# DDR4_SODIMM1.net
KiCad netlist of a schematic drawn in Altium Designer
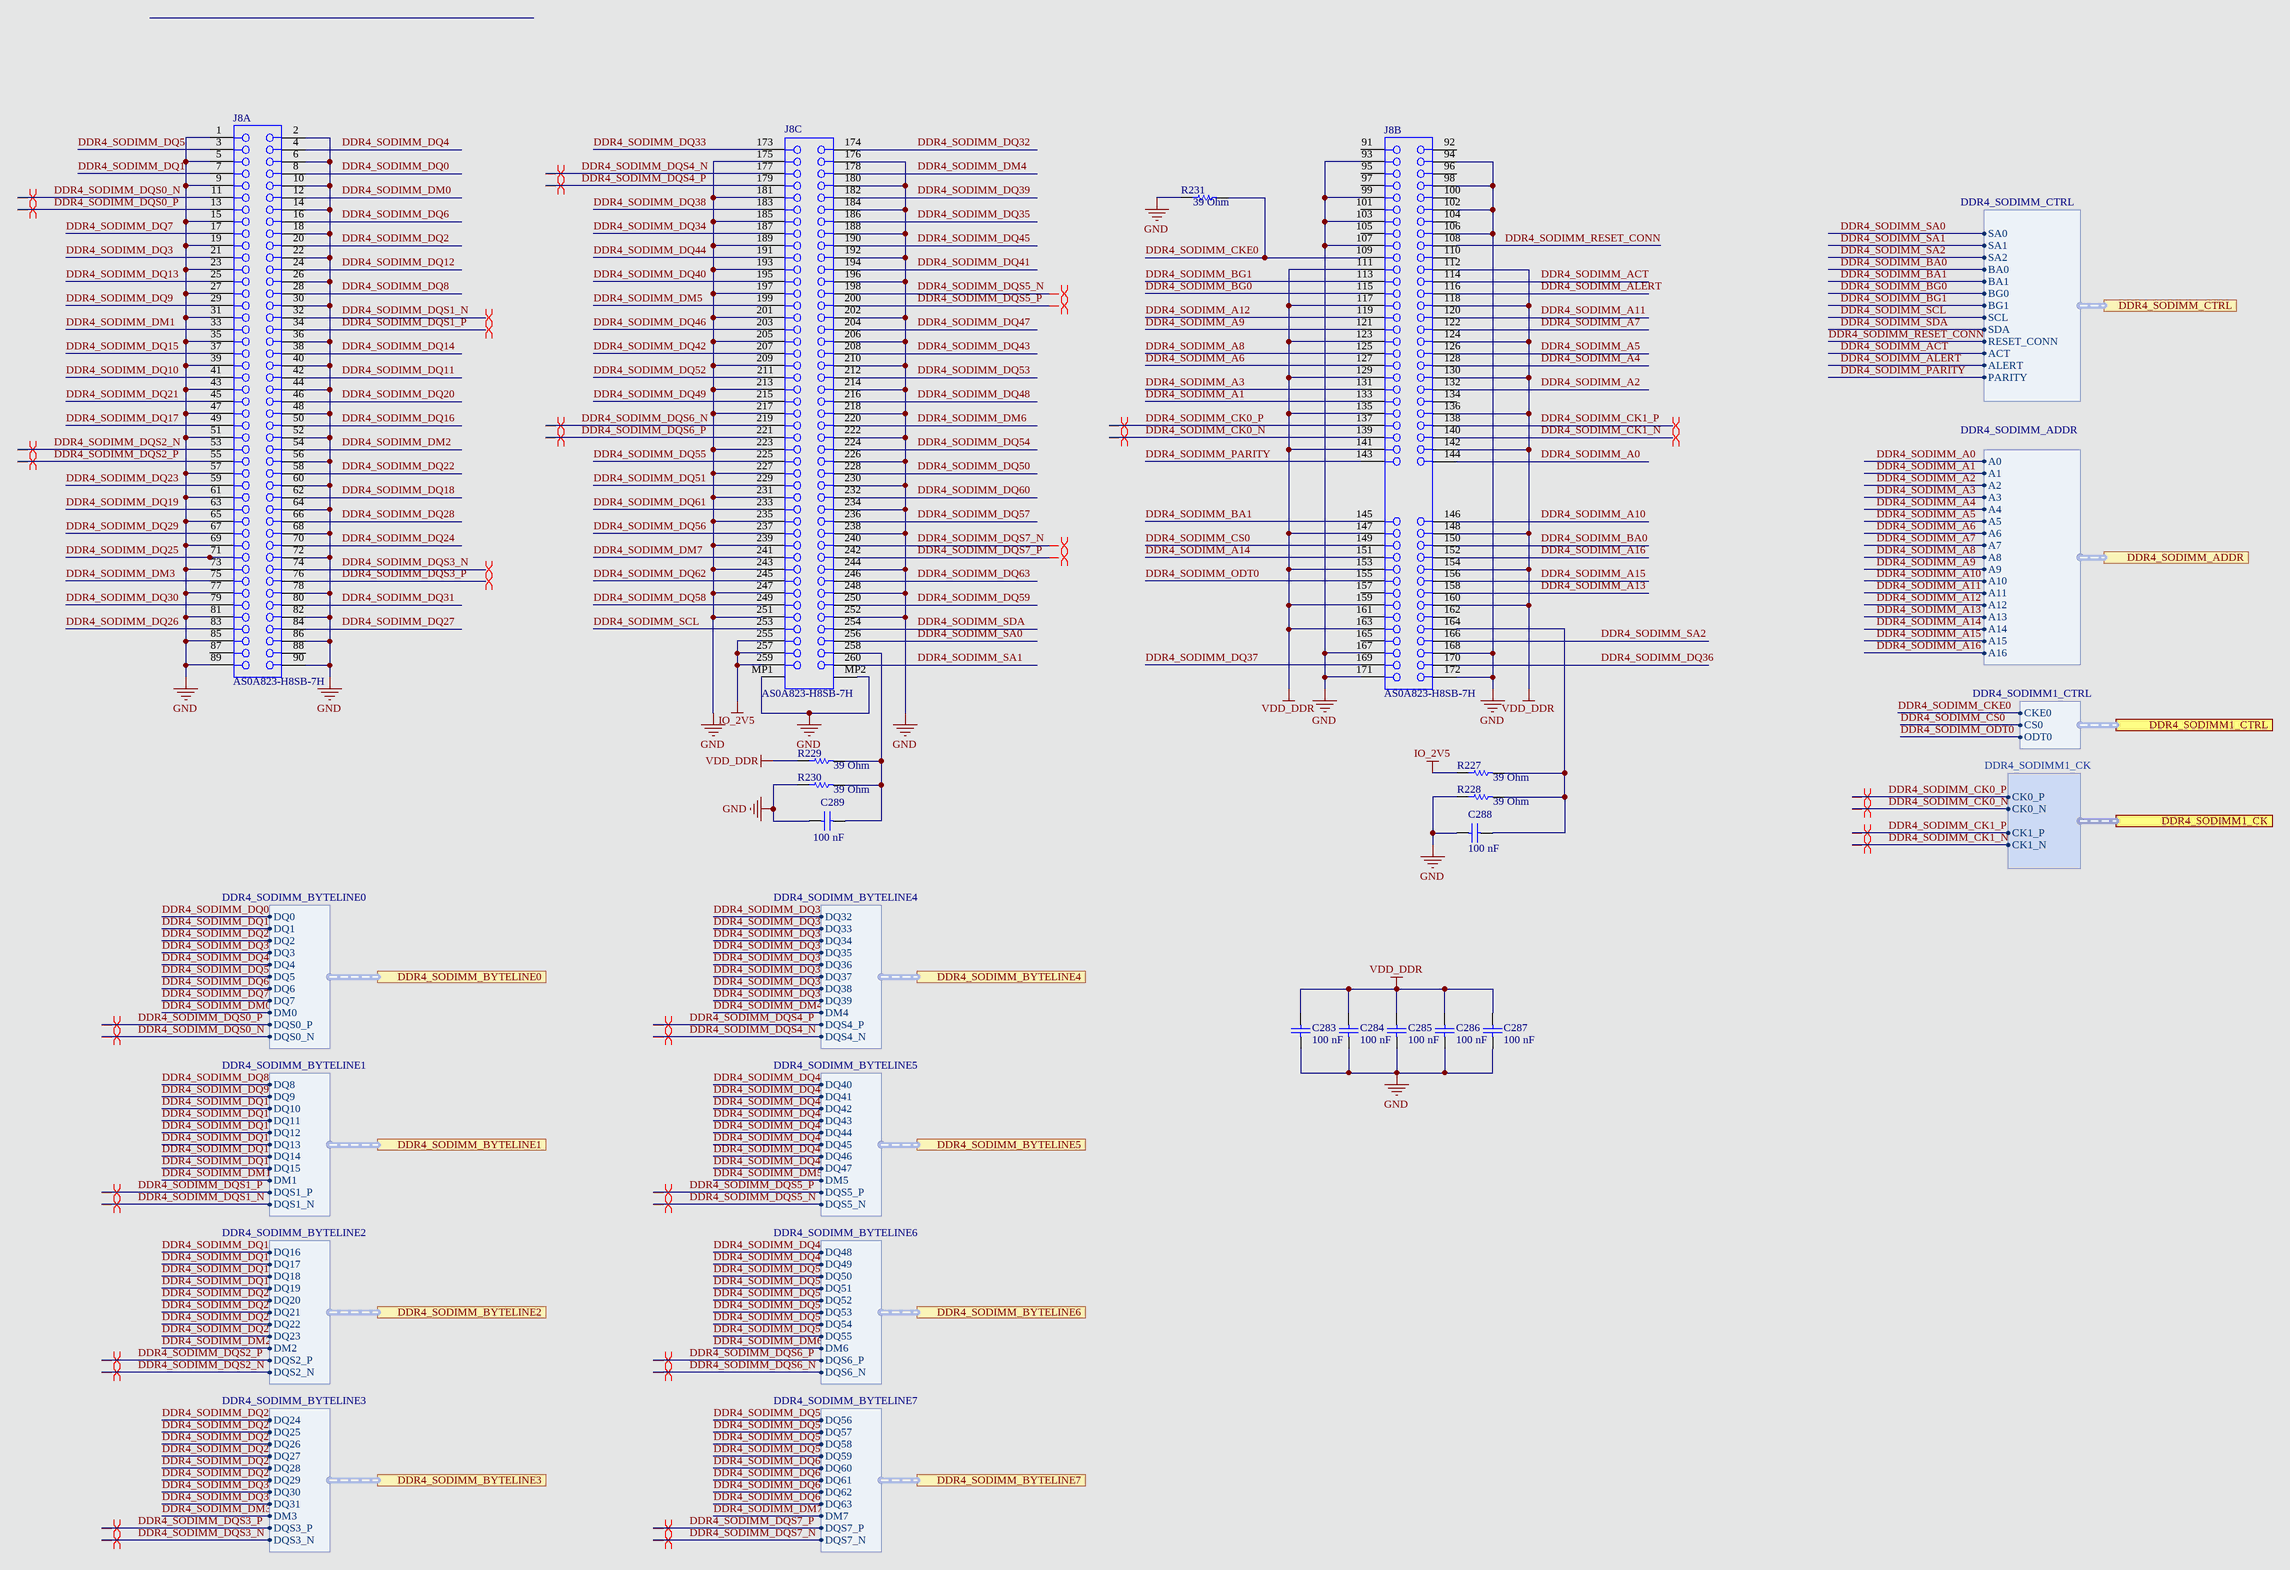
[diagram p0: DDR4_SODIMM1.SchDoc]

(export (version "E")
  (design (tool "Eeschema 10.0.6"))
  (components
    (comp (ref "C283")
      (value "C1005X7R1E104M")
      (footprint "CAPC1005X55X10LL05")
      (description "Chip Capacitor, 0.1 uF, +/- 20%, 25 V, -55 to 125 degC, 0402 (1005 Metric), RoHS, Tape and Reel")
      (fields (field (name "TOLERANCE") "20%") (field (name "CAPACITANCE") "100 nF"))
      (libsource (lib "Altium Content Vault") (part "CAP-NP-2"))
    )
    (comp (ref "C284")
      (value "C1005X7R1E104M")
      (footprint "CAPC1005X55X10LL05")
      (description "Chip Capacitor, 0.1 uF, +/- 20%, 25 V, -55 to 125 degC, 0402 (1005 Metric), RoHS, Tape and Reel")
      (fields (field (name "TOLERANCE") "20%") (field (name "CAPACITANCE") "100 nF"))
      (libsource (lib "Altium Content Vault") (part "CAP-NP-2"))
    )
    (comp (ref "C285")
      (value "C1005X7R1E104M")
      (footprint "CAPC1005X55X10LL05")
      (description "Chip Capacitor, 0.1 uF, +/- 20%, 25 V, -55 to 125 degC, 0402 (1005 Metric), RoHS, Tape and Reel")
      (fields (field (name "TOLERANCE") "20%") (field (name "CAPACITANCE") "100 nF"))
      (libsource (lib "Altium Content Vault") (part "CAP-NP-2"))
    )
    (comp (ref "C286")
      (value "C1005X7R1E104M")
      (footprint "CAPC1005X55X10LL05")
      (description "Chip Capacitor, 0.1 uF, +/- 20%, 25 V, -55 to 125 degC, 0402 (1005 Metric), RoHS, Tape and Reel")
      (fields (field (name "TOLERANCE") "20%") (field (name "CAPACITANCE") "100 nF"))
      (libsource (lib "Altium Content Vault") (part "CAP-NP-2"))
    )
    (comp (ref "C287")
      (value "C1005X7R1E104M")
      (footprint "CAPC1005X55X10LL05")
      (description "Chip Capacitor, 0.1 uF, +/- 20%, 25 V, -55 to 125 degC, 0402 (1005 Metric), RoHS, Tape and Reel")
      (fields (field (name "TOLERANCE") "20%") (field (name "CAPACITANCE") "100 nF"))
      (libsource (lib "Altium Content Vault") (part "CAP-NP-2"))
    )
    (comp (ref "C288")
      (value "C1005X7R1E104M")
      (footprint "CAPC1005X55X10LL05")
      (description "Chip Capacitor, 0.1 uF, +/- 20%, 25 V, -55 to 125 degC, 0402 (1005 Metric), RoHS, Tape and Reel")
      (fields (field (name "TOLERANCE") "20%") (field (name "CAPACITANCE") "100 nF"))
      (libsource (lib "Altium Content Vault") (part "CAP-NP-2"))
    )
    (comp (ref "C289")
      (value "C1005X7R1E104M")
      (footprint "CAPC1005X55X10LL05")
      (description "Chip Capacitor, 0.1 uF, +/- 20%, 25 V, -55 to 125 degC, 0402 (1005 Metric), RoHS, Tape and Reel")
      (fields (field (name "TOLERANCE") "20%") (field (name "CAPACITANCE") "100 nF"))
      (libsource (lib "Altium Content Vault") (part "CAP-NP-2"))
    )
    (comp (ref "J8")
      (value "AS0A823-H8SB-7H")
      (footprint "FOXC-AS0A823-H8SB-7H_V")
      (libsource (lib "") (part "CN-2S-2F-R260_1"))
    )
    (comp (ref "R227")
      (value "RC0402JR-0739RL")
      (footprint "RESC1005X40X25NL5T10")
      (description "Chip Resistor, 39 Ohm, +/- 5%, 0.063 W, -55 to 155 degC, 0402 (1005 Metric), RoHS, Tape and Reel")
      (fields (field (name "TOLERANCE") "5%") (field (name "RESISTANCE") "39 Ohm"))
      (libsource (lib "Altium Content Vault") (part "CMP-2002-07994-2"))
    )
    (comp (ref "R228")
      (value "RC0402JR-0739RL")
      (footprint "RESC1005X40X25NL5T10")
      (description "Chip Resistor, 39 Ohm, +/- 5%, 0.063 W, -55 to 155 degC, 0402 (1005 Metric), RoHS, Tape and Reel")
      (fields (field (name "TOLERANCE") "5%") (field (name "RESISTANCE") "39 Ohm"))
      (libsource (lib "Altium Content Vault") (part "CMP-2002-07994-2"))
    )
    (comp (ref "R229")
      (value "RC0402JR-0739RL")
      (footprint "RESC1005X40X25NL5T10")
      (description "Chip Resistor, 39 Ohm, +/- 5%, 0.063 W, -55 to 155 degC, 0402 (1005 Metric), RoHS, Tape and Reel")
      (fields (field (name "TOLERANCE") "5%") (field (name "RESISTANCE") "39 Ohm"))
      (libsource (lib "Altium Content Vault") (part "CMP-2002-07994-2"))
    )
    (comp (ref "R230")
      (value "RC0402JR-0739RL")
      (footprint "RESC1005X40X25NL5T10")
      (description "Chip Resistor, 39 Ohm, +/- 5%, 0.063 W, -55 to 155 degC, 0402 (1005 Metric), RoHS, Tape and Reel")
      (fields (field (name "TOLERANCE") "5%") (field (name "RESISTANCE") "39 Ohm"))
      (libsource (lib "Altium Content Vault") (part "CMP-2002-07994-2"))
    )
    (comp (ref "R231")
      (value "RC0402JR-0739RL")
      (footprint "RESC1005X40X25NL5T10")
      (description "Chip Resistor, 39 Ohm, +/- 5%, 0.063 W, -55 to 155 degC, 0402 (1005 Metric), RoHS, Tape and Reel")
      (fields (field (name "TOLERANCE") "5%") (field (name "RESISTANCE") "39 Ohm"))
      (libsource (lib "Altium Content Vault") (part "CMP-2002-07994-2"))
    )
  )
  (nets
    (net (code "13") (name "/DDR4_SODIMM_A0") (class "Default")
      (node (ref "J8") (pin "144") (pinfunction "144_144") (pintype "passive"))
    )
    (net (code "14") (name "/DDR4_SODIMM_A1") (class "Default")
      (node (ref "J8") (pin "133") (pinfunction "133_133") (pintype "passive"))
    )
    (net (code "15") (name "/DDR4_SODIMM_A2") (class "Default")
      (node (ref "J8") (pin "132") (pinfunction "132_132") (pintype "passive"))
    )
    (net (code "16") (name "/DDR4_SODIMM_A3") (class "Default")
      (node (ref "J8") (pin "131") (pinfunction "131_131") (pintype "passive"))
    )
    (net (code "17") (name "/DDR4_SODIMM_A4") (class "Default")
      (node (ref "J8") (pin "128") (pinfunction "128_128") (pintype "passive"))
    )
    (net (code "18") (name "/DDR4_SODIMM_A5") (class "Default")
      (node (ref "J8") (pin "126") (pinfunction "126_126") (pintype "passive"))
    )
    (net (code "19") (name "/DDR4_SODIMM_A6") (class "Default")
      (node (ref "J8") (pin "127") (pinfunction "127_127") (pintype "passive"))
    )
    (net (code "20") (name "/DDR4_SODIMM_A7") (class "Default")
      (node (ref "J8") (pin "122") (pinfunction "122_122") (pintype "passive"))
    )
    (net (code "21") (name "/DDR4_SODIMM_A8") (class "Default")
      (node (ref "J8") (pin "125") (pinfunction "125_125") (pintype "passive"))
    )
    (net (code "22") (name "/DDR4_SODIMM_A9") (class "Default")
      (node (ref "J8") (pin "121") (pinfunction "121_121") (pintype "passive"))
    )
    (net (code "23") (name "/DDR4_SODIMM_A10") (class "Default")
      (node (ref "J8") (pin "146") (pinfunction "146_146") (pintype "passive"))
    )
    (net (code "24") (name "/DDR4_SODIMM_A11") (class "Default")
      (node (ref "J8") (pin "120") (pinfunction "120_120") (pintype "passive"))
    )
    (net (code "25") (name "/DDR4_SODIMM_A12") (class "Default")
      (node (ref "J8") (pin "119") (pinfunction "119_119") (pintype "passive"))
    )
    (net (code "26") (name "/DDR4_SODIMM_A13") (class "Default")
      (node (ref "J8") (pin "158") (pinfunction "158_158") (pintype "passive"))
    )
    (net (code "27") (name "/DDR4_SODIMM_A14") (class "Default")
      (node (ref "J8") (pin "151") (pinfunction "151_151") (pintype "passive"))
    )
    (net (code "28") (name "/DDR4_SODIMM_A15") (class "Default")
      (node (ref "J8") (pin "156") (pinfunction "156_156") (pintype "passive"))
    )
    (net (code "29") (name "/DDR4_SODIMM_A16") (class "Default")
      (node (ref "J8") (pin "152") (pinfunction "152_152") (pintype "passive"))
    )
    (net (code "30") (name "/DDR4_SODIMM_ACT") (class "Default")
      (node (ref "J8") (pin "114") (pinfunction "114_114") (pintype "passive"))
    )
    (net (code "31") (name "/DDR4_SODIMM_ALERT") (class "Default")
      (node (ref "J8") (pin "116") (pinfunction "116_116") (pintype "passive"))
    )
    (net (code "32") (name "/DDR4_SODIMM_BA0") (class "Default")
      (node (ref "J8") (pin "150") (pinfunction "150_150") (pintype "passive"))
    )
    (net (code "33") (name "/DDR4_SODIMM_BA1") (class "Default")
      (node (ref "J8") (pin "145") (pinfunction "145_145") (pintype "passive"))
    )
    (net (code "34") (name "/DDR4_SODIMM_BG0") (class "Default")
      (node (ref "J8") (pin "115") (pinfunction "115_115") (pintype "passive"))
    )
    (net (code "35") (name "/DDR4_SODIMM_BG1") (class "Default")
      (node (ref "J8") (pin "113") (pinfunction "113_113") (pintype "passive"))
    )
    (net (code "36") (name "/DDR4_SODIMM_CK0_N") (class "Default")
      (node (ref "J8") (pin "139") (pinfunction "139_139") (pintype "passive"))
    )
    (net (code "37") (name "/DDR4_SODIMM_CK0_P") (class "Default")
      (node (ref "J8") (pin "137") (pinfunction "137_137") (pintype "passive"))
    )
    (net (code "38") (name "/DDR4_SODIMM_CK1_N") (class "Default")
      (node (ref "J8") (pin "140") (pinfunction "140_140") (pintype "passive"))
    )
    (net (code "39") (name "/DDR4_SODIMM_CK1_P") (class "Default")
      (node (ref "J8") (pin "138") (pinfunction "138_138") (pintype "passive"))
    )
    (net (code "40") (name "/DDR4_SODIMM_CKE0") (class "Default")
      (node (ref "J8") (pin "109") (pinfunction "109_109") (pintype "passive"))
      (node (ref "R231") (pin "2") (pinfunction "2_2") (pintype "passive"))
    )
    (net (code "41") (name "/DDR4_SODIMM_CS0") (class "Default")
      (node (ref "J8") (pin "149") (pinfunction "149_149") (pintype "passive"))
    )
    (net (code "42") (name "/DDR4_SODIMM_DM0") (class "Default")
      (node (ref "J8") (pin "12") (pinfunction "12_12") (pintype "passive"))
    )
    (net (code "43") (name "/DDR4_SODIMM_DM1") (class "Default")
      (node (ref "J8") (pin "33") (pinfunction "33_33") (pintype "passive"))
    )
    (net (code "44") (name "/DDR4_SODIMM_DM2") (class "Default")
      (node (ref "J8") (pin "54") (pinfunction "54_54") (pintype "passive"))
    )
    (net (code "45") (name "/DDR4_SODIMM_DM3") (class "Default")
      (node (ref "J8") (pin "75") (pinfunction "75_75") (pintype "passive"))
    )
    (net (code "46") (name "/DDR4_SODIMM_DM4") (class "Default")
      (node (ref "J8") (pin "178") (pinfunction "178_178") (pintype "passive"))
    )
    (net (code "47") (name "/DDR4_SODIMM_DM5") (class "Default")
      (node (ref "J8") (pin "199") (pinfunction "199_199") (pintype "passive"))
    )
    (net (code "48") (name "/DDR4_SODIMM_DM6") (class "Default")
      (node (ref "J8") (pin "220") (pinfunction "220_220") (pintype "passive"))
    )
    (net (code "49") (name "/DDR4_SODIMM_DM7") (class "Default")
      (node (ref "J8") (pin "241") (pinfunction "241_241") (pintype "passive"))
    )
    (net (code "50") (name "/DDR4_SODIMM_DQ0") (class "Default")
      (node (ref "J8") (pin "8") (pinfunction "8_8") (pintype "passive"))
    )
    (net (code "51") (name "/DDR4_SODIMM_DQ1") (class "Default")
      (node (ref "J8") (pin "7") (pinfunction "7_7") (pintype "passive"))
    )
    (net (code "52") (name "/DDR4_SODIMM_DQ2") (class "Default")
      (node (ref "J8") (pin "20") (pinfunction "20_20") (pintype "passive"))
    )
    (net (code "53") (name "/DDR4_SODIMM_DQ3") (class "Default")
      (node (ref "J8") (pin "21") (pinfunction "21_21") (pintype "passive"))
    )
    (net (code "54") (name "/DDR4_SODIMM_DQ4") (class "Default")
      (node (ref "J8") (pin "4") (pinfunction "4_4") (pintype "passive"))
    )
    (net (code "55") (name "/DDR4_SODIMM_DQ5") (class "Default")
      (node (ref "J8") (pin "3") (pinfunction "3_3") (pintype "passive"))
    )
    (net (code "56") (name "/DDR4_SODIMM_DQ6") (class "Default")
      (node (ref "J8") (pin "16") (pinfunction "16_16") (pintype "passive"))
    )
    (net (code "57") (name "/DDR4_SODIMM_DQ7") (class "Default")
      (node (ref "J8") (pin "17") (pinfunction "17_17") (pintype "passive"))
    )
    (net (code "58") (name "/DDR4_SODIMM_DQ8") (class "Default")
      (node (ref "J8") (pin "28") (pinfunction "28_28") (pintype "passive"))
    )
    (net (code "59") (name "/DDR4_SODIMM_DQ9") (class "Default")
      (node (ref "J8") (pin "29") (pinfunction "29_29") (pintype "passive"))
    )
    (net (code "60") (name "/DDR4_SODIMM_DQ10") (class "Default")
      (node (ref "J8") (pin "41") (pinfunction "41_41") (pintype "passive"))
    )
    (net (code "61") (name "/DDR4_SODIMM_DQ11") (class "Default")
      (node (ref "J8") (pin "42") (pinfunction "42_42") (pintype "passive"))
    )
    (net (code "62") (name "/DDR4_SODIMM_DQ12") (class "Default")
      (node (ref "J8") (pin "24") (pinfunction "24_24") (pintype "passive"))
    )
    (net (code "63") (name "/DDR4_SODIMM_DQ13") (class "Default")
      (node (ref "J8") (pin "25") (pinfunction "25_25") (pintype "passive"))
    )
    (net (code "64") (name "/DDR4_SODIMM_DQ14") (class "Default")
      (node (ref "J8") (pin "38") (pinfunction "38_38") (pintype "passive"))
    )
    (net (code "65") (name "/DDR4_SODIMM_DQ15") (class "Default")
      (node (ref "J8") (pin "37") (pinfunction "37_37") (pintype "passive"))
    )
    (net (code "66") (name "/DDR4_SODIMM_DQ16") (class "Default")
      (node (ref "J8") (pin "50") (pinfunction "50_50") (pintype "passive"))
    )
    (net (code "67") (name "/DDR4_SODIMM_DQ17") (class "Default")
      (node (ref "J8") (pin "49") (pinfunction "49_49") (pintype "passive"))
    )
    (net (code "68") (name "/DDR4_SODIMM_DQ18") (class "Default")
      (node (ref "J8") (pin "62") (pinfunction "62_62") (pintype "passive"))
    )
    (net (code "69") (name "/DDR4_SODIMM_DQ19") (class "Default")
      (node (ref "J8") (pin "63") (pinfunction "63_63") (pintype "passive"))
    )
    (net (code "70") (name "/DDR4_SODIMM_DQ20") (class "Default")
      (node (ref "J8") (pin "46") (pinfunction "46_46") (pintype "passive"))
    )
    (net (code "71") (name "/DDR4_SODIMM_DQ21") (class "Default")
      (node (ref "J8") (pin "45") (pinfunction "45_45") (pintype "passive"))
    )
    (net (code "72") (name "/DDR4_SODIMM_DQ22") (class "Default")
      (node (ref "J8") (pin "58") (pinfunction "58_58") (pintype "passive"))
    )
    (net (code "73") (name "/DDR4_SODIMM_DQ23") (class "Default")
      (node (ref "J8") (pin "59") (pinfunction "59_59") (pintype "passive"))
    )
    (net (code "74") (name "/DDR4_SODIMM_DQ24") (class "Default")
      (node (ref "J8") (pin "70") (pinfunction "70_70") (pintype "passive"))
    )
    (net (code "75") (name "/DDR4_SODIMM_DQ25") (class "Default")
      (node (ref "J8") (pin "71") (pinfunction "71_71") (pintype "passive"))
    )
    (net (code "76") (name "/DDR4_SODIMM_DQ26") (class "Default")
      (node (ref "J8") (pin "83") (pinfunction "83_83") (pintype "passive"))
    )
    (net (code "77") (name "/DDR4_SODIMM_DQ27") (class "Default")
      (node (ref "J8") (pin "84") (pinfunction "84_84") (pintype "passive"))
    )
    (net (code "78") (name "/DDR4_SODIMM_DQ28") (class "Default")
      (node (ref "J8") (pin "66") (pinfunction "66_66") (pintype "passive"))
    )
    (net (code "79") (name "/DDR4_SODIMM_DQ29") (class "Default")
      (node (ref "J8") (pin "67") (pinfunction "67_67") (pintype "passive"))
    )
    (net (code "80") (name "/DDR4_SODIMM_DQ30") (class "Default")
      (node (ref "J8") (pin "79") (pinfunction "79_79") (pintype "passive"))
    )
    (net (code "81") (name "/DDR4_SODIMM_DQ31") (class "Default")
      (node (ref "J8") (pin "80") (pinfunction "80_80") (pintype "passive"))
    )
    (net (code "82") (name "/DDR4_SODIMM_DQ32") (class "Default")
      (node (ref "J8") (pin "174") (pinfunction "174_174") (pintype "passive"))
    )
    (net (code "83") (name "/DDR4_SODIMM_DQ33") (class "Default")
      (node (ref "J8") (pin "173") (pinfunction "173_173") (pintype "passive"))
    )
    (net (code "84") (name "/DDR4_SODIMM_DQ34") (class "Default")
      (node (ref "J8") (pin "187") (pinfunction "187_187") (pintype "passive"))
    )
    (net (code "85") (name "/DDR4_SODIMM_DQ35") (class "Default")
      (node (ref "J8") (pin "186") (pinfunction "186_186") (pintype "passive"))
    )
    (net (code "86") (name "/DDR4_SODIMM_DQ36") (class "Default")
      (node (ref "J8") (pin "170") (pinfunction "170_170") (pintype "passive"))
    )
    (net (code "87") (name "/DDR4_SODIMM_DQ37") (class "Default")
      (node (ref "J8") (pin "169") (pinfunction "169_169") (pintype "passive"))
    )
    (net (code "88") (name "/DDR4_SODIMM_DQ38") (class "Default")
      (node (ref "J8") (pin "183") (pinfunction "183_183") (pintype "passive"))
    )
    (net (code "89") (name "/DDR4_SODIMM_DQ39") (class "Default")
      (node (ref "J8") (pin "182") (pinfunction "182_182") (pintype "passive"))
    )
    (net (code "90") (name "/DDR4_SODIMM_DQ40") (class "Default")
      (node (ref "J8") (pin "195") (pinfunction "195_195") (pintype "passive"))
    )
    (net (code "91") (name "/DDR4_SODIMM_DQ41") (class "Default")
      (node (ref "J8") (pin "194") (pinfunction "194_194") (pintype "passive"))
    )
    (net (code "92") (name "/DDR4_SODIMM_DQ42") (class "Default")
      (node (ref "J8") (pin "207") (pinfunction "207_207") (pintype "passive"))
    )
    (net (code "93") (name "/DDR4_SODIMM_DQ43") (class "Default")
      (node (ref "J8") (pin "208") (pinfunction "208_208") (pintype "passive"))
    )
    (net (code "94") (name "/DDR4_SODIMM_DQ44") (class "Default")
      (node (ref "J8") (pin "191") (pinfunction "191_191") (pintype "passive"))
    )
    (net (code "95") (name "/DDR4_SODIMM_DQ45") (class "Default")
      (node (ref "J8") (pin "190") (pinfunction "190_190") (pintype "passive"))
    )
    (net (code "96") (name "/DDR4_SODIMM_DQ46") (class "Default")
      (node (ref "J8") (pin "203") (pinfunction "203_203") (pintype "passive"))
    )
    (net (code "97") (name "/DDR4_SODIMM_DQ47") (class "Default")
      (node (ref "J8") (pin "204") (pinfunction "204_204") (pintype "passive"))
    )
    (net (code "98") (name "/DDR4_SODIMM_DQ48") (class "Default")
      (node (ref "J8") (pin "216") (pinfunction "216_216") (pintype "passive"))
    )
    (net (code "99") (name "/DDR4_SODIMM_DQ49") (class "Default")
      (node (ref "J8") (pin "215") (pinfunction "215_215") (pintype "passive"))
    )
    (net (code "100") (name "/DDR4_SODIMM_DQ50") (class "Default")
      (node (ref "J8") (pin "228") (pinfunction "228_228") (pintype "passive"))
    )
    (net (code "101") (name "/DDR4_SODIMM_DQ51") (class "Default")
      (node (ref "J8") (pin "229") (pinfunction "229_229") (pintype "passive"))
    )
    (net (code "102") (name "/DDR4_SODIMM_DQ52") (class "Default")
      (node (ref "J8") (pin "211") (pinfunction "211_211") (pintype "passive"))
    )
    (net (code "103") (name "/DDR4_SODIMM_DQ53") (class "Default")
      (node (ref "J8") (pin "212") (pinfunction "212_212") (pintype "passive"))
    )
    (net (code "104") (name "/DDR4_SODIMM_DQ54") (class "Default")
      (node (ref "J8") (pin "224") (pinfunction "224_224") (pintype "passive"))
    )
    (net (code "105") (name "/DDR4_SODIMM_DQ55") (class "Default")
      (node (ref "J8") (pin "225") (pinfunction "225_225") (pintype "passive"))
    )
    (net (code "106") (name "/DDR4_SODIMM_DQ56") (class "Default")
      (node (ref "J8") (pin "237") (pinfunction "237_237") (pintype "passive"))
    )
    (net (code "107") (name "/DDR4_SODIMM_DQ57") (class "Default")
      (node (ref "J8") (pin "236") (pinfunction "236_236") (pintype "passive"))
    )
    (net (code "108") (name "/DDR4_SODIMM_DQ58") (class "Default")
      (node (ref "J8") (pin "249") (pinfunction "249_249") (pintype "passive"))
    )
    (net (code "109") (name "/DDR4_SODIMM_DQ59") (class "Default")
      (node (ref "J8") (pin "250") (pinfunction "250_250") (pintype "passive"))
    )
    (net (code "110") (name "/DDR4_SODIMM_DQ60") (class "Default")
      (node (ref "J8") (pin "232") (pinfunction "232_232") (pintype "passive"))
    )
    (net (code "111") (name "/DDR4_SODIMM_DQ61") (class "Default")
      (node (ref "J8") (pin "233") (pinfunction "233_233") (pintype "passive"))
    )
    (net (code "112") (name "/DDR4_SODIMM_DQ62") (class "Default")
      (node (ref "J8") (pin "245") (pinfunction "245_245") (pintype "passive"))
    )
    (net (code "113") (name "/DDR4_SODIMM_DQ63") (class "Default")
      (node (ref "J8") (pin "246") (pinfunction "246_246") (pintype "passive"))
    )
    (net (code "114") (name "/DDR4_SODIMM_DQS0_N") (class "Default")
      (node (ref "J8") (pin "11") (pinfunction "11_11") (pintype "passive"))
    )
    (net (code "115") (name "/DDR4_SODIMM_DQS0_P") (class "Default")
      (node (ref "J8") (pin "13") (pinfunction "13_13") (pintype "passive"))
    )
    (net (code "116") (name "/DDR4_SODIMM_DQS1_N") (class "Default")
      (node (ref "J8") (pin "32") (pinfunction "32_32") (pintype "passive"))
    )
    (net (code "117") (name "/DDR4_SODIMM_DQS1_P") (class "Default")
      (node (ref "J8") (pin "34") (pinfunction "34_34") (pintype "passive"))
    )
    (net (code "118") (name "/DDR4_SODIMM_DQS2_N") (class "Default")
      (node (ref "J8") (pin "53") (pinfunction "53_53") (pintype "passive"))
    )
    (net (code "119") (name "/DDR4_SODIMM_DQS2_P") (class "Default")
      (node (ref "J8") (pin "55") (pinfunction "55_55") (pintype "passive"))
    )
    (net (code "120") (name "/DDR4_SODIMM_DQS3_N") (class "Default")
      (node (ref "J8") (pin "74") (pinfunction "74_74") (pintype "passive"))
    )
    (net (code "121") (name "/DDR4_SODIMM_DQS3_P") (class "Default")
      (node (ref "J8") (pin "76") (pinfunction "76_76") (pintype "passive"))
    )
    (net (code "122") (name "/DDR4_SODIMM_DQS4_N") (class "Default")
      (node (ref "J8") (pin "177") (pinfunction "177_177") (pintype "passive"))
    )
    (net (code "123") (name "/DDR4_SODIMM_DQS4_P") (class "Default")
      (node (ref "J8") (pin "179") (pinfunction "179_179") (pintype "passive"))
    )
    (net (code "124") (name "/DDR4_SODIMM_DQS5_N") (class "Default")
      (node (ref "J8") (pin "198") (pinfunction "198_198") (pintype "passive"))
    )
    (net (code "125") (name "/DDR4_SODIMM_DQS5_P") (class "Default")
      (node (ref "J8") (pin "200") (pinfunction "200_200") (pintype "passive"))
    )
    (net (code "126") (name "/DDR4_SODIMM_DQS6_N") (class "Default")
      (node (ref "J8") (pin "219") (pinfunction "219_219") (pintype "passive"))
    )
    (net (code "127") (name "/DDR4_SODIMM_DQS6_P") (class "Default")
      (node (ref "J8") (pin "221") (pinfunction "221_221") (pintype "passive"))
    )
    (net (code "128") (name "/DDR4_SODIMM_DQS7_N") (class "Default")
      (node (ref "J8") (pin "240") (pinfunction "240_240") (pintype "passive"))
    )
    (net (code "129") (name "/DDR4_SODIMM_DQS7_P") (class "Default")
      (node (ref "J8") (pin "242") (pinfunction "242_242") (pintype "passive"))
    )
    (net (code "130") (name "/DDR4_SODIMM_ODT0") (class "Default")
      (node (ref "J8") (pin "155") (pinfunction "155_155") (pintype "passive"))
    )
    (net (code "131") (name "/DDR4_SODIMM_PARITY") (class "Default")
      (node (ref "J8") (pin "143") (pinfunction "143_143") (pintype "passive"))
    )
    (net (code "132") (name "/DDR4_SODIMM_RESET_CONN") (class "Default")
      (node (ref "J8") (pin "108") (pinfunction "108_108") (pintype "passive"))
    )
    (net (code "133") (name "/DDR4_SODIMM_SA0") (class "Default")
      (node (ref "J8") (pin "256") (pinfunction "256_256") (pintype "passive"))
    )
    (net (code "134") (name "/DDR4_SODIMM_SA1") (class "Default")
      (node (ref "J8") (pin "260") (pinfunction "260_260") (pintype "passive"))
    )
    (net (code "135") (name "/DDR4_SODIMM_SA2") (class "Default")
      (node (ref "J8") (pin "166") (pinfunction "166_166") (pintype "passive"))
    )
    (net (code "136") (name "/DDR4_SODIMM_SCL") (class "Default")
      (node (ref "J8") (pin "253") (pinfunction "253_253") (pintype "passive"))
    )
    (net (code "137") (name "/DDR4_SODIMM_SDA") (class "Default")
      (node (ref "J8") (pin "254") (pinfunction "254_254") (pintype "passive"))
    )
    (net (code "150") (name "GND") (class "Default")
      (node (ref "C283") (pin "2") (pinfunction "2_2") (pintype "passive"))
      (node (ref "C284") (pin "2") (pinfunction "2_2") (pintype "passive"))
      (node (ref "C285") (pin "2") (pinfunction "2_2") (pintype "passive"))
      (node (ref "C286") (pin "2") (pinfunction "2_2") (pintype "passive"))
      (node (ref "C287") (pin "2") (pinfunction "2_2") (pintype "passive"))
      (node (ref "C288") (pin "1") (pinfunction "1_1") (pintype "passive"))
      (node (ref "C289") (pin "2") (pinfunction "2_2") (pintype "passive"))
      (node (ref "J8") (pin "1") (pinfunction "1_1") (pintype "passive"))
      (node (ref "J8") (pin "10") (pinfunction "10_10") (pintype "passive"))
      (node (ref "J8") (pin "102") (pinfunction "102_102") (pintype "passive"))
      (node (ref "J8") (pin "103") (pinfunction "103_103") (pintype "passive"))
      (node (ref "J8") (pin "106") (pinfunction "106_106") (pintype "passive"))
      (node (ref "J8") (pin "107") (pinfunction "107_107") (pintype "passive"))
      (node (ref "J8") (pin "14") (pinfunction "14_14") (pintype "passive"))
      (node (ref "J8") (pin "15") (pinfunction "15_15") (pintype "passive"))
      (node (ref "J8") (pin "167") (pinfunction "167_167") (pintype "passive"))
      (node (ref "J8") (pin "168") (pinfunction "168_168") (pintype "passive"))
      (node (ref "J8") (pin "171") (pinfunction "171_171") (pintype "passive"))
      (node (ref "J8") (pin "172") (pinfunction "172_172") (pintype "passive"))
      (node (ref "J8") (pin "175") (pinfunction "175_175") (pintype "passive"))
      (node (ref "J8") (pin "176") (pinfunction "176_176") (pintype "passive"))
      (node (ref "J8") (pin "18") (pinfunction "18_18") (pintype "passive"))
      (node (ref "J8") (pin "180") (pinfunction "180_180") (pintype "passive"))
      (node (ref "J8") (pin "181") (pinfunction "181_181") (pintype "passive"))
      (node (ref "J8") (pin "184") (pinfunction "184_184") (pintype "passive"))
      (node (ref "J8") (pin "185") (pinfunction "185_185") (pintype "passive"))
      (node (ref "J8") (pin "188") (pinfunction "188_188") (pintype "passive"))
      (node (ref "J8") (pin "189") (pinfunction "189_189") (pintype "passive"))
      (node (ref "J8") (pin "19") (pinfunction "19_19") (pintype "passive"))
      (node (ref "J8") (pin "192") (pinfunction "192_192") (pintype "passive"))
      (node (ref "J8") (pin "193") (pinfunction "193_193") (pintype "passive"))
      (node (ref "J8") (pin "196") (pinfunction "196_196") (pintype "passive"))
      (node (ref "J8") (pin "197") (pinfunction "197_197") (pintype "passive"))
      (node (ref "J8") (pin "2") (pinfunction "2_2") (pintype "passive"))
      (node (ref "J8") (pin "201") (pinfunction "201_201") (pintype "passive"))
      (node (ref "J8") (pin "202") (pinfunction "202_202") (pintype "passive"))
      (node (ref "J8") (pin "205") (pinfunction "205_205") (pintype "passive"))
      (node (ref "J8") (pin "206") (pinfunction "206_206") (pintype "passive"))
      (node (ref "J8") (pin "209") (pinfunction "209_209") (pintype "passive"))
      (node (ref "J8") (pin "210") (pinfunction "210_210") (pintype "passive"))
      (node (ref "J8") (pin "213") (pinfunction "213_213") (pintype "passive"))
      (node (ref "J8") (pin "214") (pinfunction "214_214") (pintype "passive"))
      (node (ref "J8") (pin "217") (pinfunction "217_217") (pintype "passive"))
      (node (ref "J8") (pin "218") (pinfunction "218_218") (pintype "passive"))
      (node (ref "J8") (pin "22") (pinfunction "22_22") (pintype "passive"))
      (node (ref "J8") (pin "222") (pinfunction "222_222") (pintype "passive"))
      (node (ref "J8") (pin "223") (pinfunction "223_223") (pintype "passive"))
      (node (ref "J8") (pin "226") (pinfunction "226_226") (pintype "passive"))
      (node (ref "J8") (pin "227") (pinfunction "227_227") (pintype "passive"))
      (node (ref "J8") (pin "23") (pinfunction "23_23") (pintype "passive"))
      (node (ref "J8") (pin "230") (pinfunction "230_230") (pintype "passive"))
      (node (ref "J8") (pin "231") (pinfunction "231_231") (pintype "passive"))
      (node (ref "J8") (pin "234") (pinfunction "234_234") (pintype "passive"))
      (node (ref "J8") (pin "235") (pinfunction "235_235") (pintype "passive"))
      (node (ref "J8") (pin "238") (pinfunction "238_238") (pintype "passive"))
      (node (ref "J8") (pin "239") (pinfunction "239_239") (pintype "passive"))
      (node (ref "J8") (pin "243") (pinfunction "243_243") (pintype "passive"))
      (node (ref "J8") (pin "244") (pinfunction "244_244") (pintype "passive"))
      (node (ref "J8") (pin "247") (pinfunction "247_247") (pintype "passive"))
      (node (ref "J8") (pin "248") (pinfunction "248_248") (pintype "passive"))
      (node (ref "J8") (pin "251") (pinfunction "251_251") (pintype "passive"))
      (node (ref "J8") (pin "252") (pinfunction "252_252") (pintype "passive"))
      (node (ref "J8") (pin "26") (pinfunction "26_26") (pintype "passive"))
      (node (ref "J8") (pin "27") (pinfunction "27_27") (pintype "passive"))
      (node (ref "J8") (pin "30") (pinfunction "30_30") (pintype "passive"))
      (node (ref "J8") (pin "31") (pinfunction "31_31") (pintype "passive"))
      (node (ref "J8") (pin "35") (pinfunction "35_35") (pintype "passive"))
      (node (ref "J8") (pin "36") (pinfunction "36_36") (pintype "passive"))
      (node (ref "J8") (pin "39") (pinfunction "39_39") (pintype "passive"))
      (node (ref "J8") (pin "40") (pinfunction "40_40") (pintype "passive"))
      (node (ref "J8") (pin "43") (pinfunction "43_43") (pintype "passive"))
      (node (ref "J8") (pin "44") (pinfunction "44_44") (pintype "passive"))
      (node (ref "J8") (pin "47") (pinfunction "47_47") (pintype "passive"))
      (node (ref "J8") (pin "48") (pinfunction "48_48") (pintype "passive"))
      (node (ref "J8") (pin "5") (pinfunction "5_5") (pintype "passive"))
      (node (ref "J8") (pin "51") (pinfunction "51_51") (pintype "passive"))
      (node (ref "J8") (pin "52") (pinfunction "52_52") (pintype "passive"))
      (node (ref "J8") (pin "56") (pinfunction "56_56") (pintype "passive"))
      (node (ref "J8") (pin "57") (pinfunction "57_57") (pintype "passive"))
      (node (ref "J8") (pin "6") (pinfunction "6_6") (pintype "passive"))
      (node (ref "J8") (pin "60") (pinfunction "60_60") (pintype "passive"))
      (node (ref "J8") (pin "61") (pinfunction "61_61") (pintype "passive"))
      (node (ref "J8") (pin "64") (pinfunction "64_64") (pintype "passive"))
      (node (ref "J8") (pin "65") (pinfunction "65_65") (pintype "passive"))
      (node (ref "J8") (pin "68") (pinfunction "68_68") (pintype "passive"))
      (node (ref "J8") (pin "69") (pinfunction "69_69") (pintype "passive"))
      (node (ref "J8") (pin "72") (pinfunction "72_72") (pintype "passive"))
      (node (ref "J8") (pin "73") (pinfunction "73_73") (pintype "passive"))
      (node (ref "J8") (pin "77") (pinfunction "77_77") (pintype "passive"))
      (node (ref "J8") (pin "78") (pinfunction "78_78") (pintype "passive"))
      (node (ref "J8") (pin "81") (pinfunction "81_81") (pintype "passive"))
      (node (ref "J8") (pin "82") (pinfunction "82_82") (pintype "passive"))
      (node (ref "J8") (pin "85") (pinfunction "85_85") (pintype "passive"))
      (node (ref "J8") (pin "86") (pinfunction "86_86") (pintype "passive"))
      (node (ref "J8") (pin "89") (pinfunction "89_89") (pintype "passive"))
      (node (ref "J8") (pin "9") (pinfunction "9_9") (pintype "passive"))
      (node (ref "J8") (pin "90") (pinfunction "90_90") (pintype "passive"))
      (node (ref "J8") (pin "93") (pinfunction "93_93") (pintype "passive"))
      (node (ref "J8") (pin "94") (pinfunction "94_94") (pintype "passive"))
      (node (ref "J8") (pin "98") (pinfunction "98_98") (pintype "passive"))
      (node (ref "J8") (pin "99") (pinfunction "99_99") (pintype "passive"))
      (node (ref "J8") (pin "MP1") (pinfunction "MP1_MP1") (pintype "passive"))
      (node (ref "J8") (pin "MP2") (pinfunction "MP2_MP2") (pintype "passive"))
      (node (ref "R228") (pin "1") (pinfunction "1_1") (pintype "passive"))
      (node (ref "R230") (pin "1") (pinfunction "1_1") (pintype "passive"))
      (node (ref "R231") (pin "1") (pinfunction "1_1") (pintype "passive"))
    )
    (net (code "151") (name "IO_2V5") (class "Default")
      (node (ref "J8") (pin "255") (pinfunction "255_255") (pintype "passive"))
      (node (ref "J8") (pin "257") (pinfunction "257_257") (pintype "passive"))
      (node (ref "J8") (pin "259") (pinfunction "259_259") (pintype "passive"))
      (node (ref "R227") (pin "1") (pinfunction "1_1") (pintype "passive"))
    )
    (net (code "152") (name "Net-(C288-Pad2)") (class "Default")
      (node (ref "C288") (pin "2") (pinfunction "2_2") (pintype "passive"))
      (node (ref "J8") (pin "164") (pinfunction "164_164") (pintype "passive"))
      (node (ref "R227") (pin "2") (pinfunction "2_2") (pintype "passive"))
      (node (ref "R228") (pin "2") (pinfunction "2_2") (pintype "passive"))
    )
    (net (code "153") (name "Net-(C289-Pad1)") (class "Default")
      (node (ref "C289") (pin "1") (pinfunction "1_1") (pintype "passive"))
      (node (ref "J8") (pin "258") (pinfunction "258_258") (pintype "passive"))
      (node (ref "R229") (pin "2") (pinfunction "2_2") (pintype "passive"))
      (node (ref "R230") (pin "2") (pinfunction "2_2") (pintype "passive"))
    )
    (net (code "154") (name "VDD_DDR") (class "Default")
      (node (ref "C283") (pin "1") (pinfunction "1_1") (pintype "passive"))
      (node (ref "C284") (pin "1") (pinfunction "1_1") (pintype "passive"))
      (node (ref "C285") (pin "1") (pinfunction "1_1") (pintype "passive"))
      (node (ref "C286") (pin "1") (pinfunction "1_1") (pintype "passive"))
      (node (ref "C287") (pin "1") (pinfunction "1_1") (pintype "passive"))
      (node (ref "J8") (pin "111") (pinfunction "111_111") (pintype "passive"))
      (node (ref "J8") (pin "112") (pinfunction "112_112") (pintype "passive"))
      (node (ref "J8") (pin "117") (pinfunction "117_117") (pintype "passive"))
      (node (ref "J8") (pin "118") (pinfunction "118_118") (pintype "passive"))
      (node (ref "J8") (pin "123") (pinfunction "123_123") (pintype "passive"))
      (node (ref "J8") (pin "124") (pinfunction "124_124") (pintype "passive"))
      (node (ref "J8") (pin "129") (pinfunction "129_129") (pintype "passive"))
      (node (ref "J8") (pin "130") (pinfunction "130_130") (pintype "passive"))
      (node (ref "J8") (pin "135") (pinfunction "135_135") (pintype "passive"))
      (node (ref "J8") (pin "136") (pinfunction "136_136") (pintype "passive"))
      (node (ref "J8") (pin "141") (pinfunction "141_141") (pintype "passive"))
      (node (ref "J8") (pin "142") (pinfunction "142_142") (pintype "passive"))
      (node (ref "J8") (pin "147") (pinfunction "147_147") (pintype "passive"))
      (node (ref "J8") (pin "148") (pinfunction "148_148") (pintype "passive"))
      (node (ref "J8") (pin "153") (pinfunction "153_153") (pintype "passive"))
      (node (ref "J8") (pin "154") (pinfunction "154_154") (pintype "passive"))
      (node (ref "J8") (pin "159") (pinfunction "159_159") (pintype "passive"))
      (node (ref "J8") (pin "160") (pinfunction "160_160") (pintype "passive"))
      (node (ref "J8") (pin "163") (pinfunction "163_163") (pintype "passive"))
      (node (ref "R229") (pin "1") (pinfunction "1_1") (pintype "passive"))
    )
    (net (code "155") (name "unconnected-(J8-Pad87)") (class "Default")
      (node (ref "J8") (pin "87") (pinfunction "87_87") (pintype "passive"))
    )
    (net (code "156") (name "unconnected-(J8-Pad88)") (class "Default")
      (node (ref "J8") (pin "88") (pinfunction "88_88") (pintype "passive"))
    )
    (net (code "157") (name "unconnected-(J8-Pad91)") (class "Default")
      (node (ref "J8") (pin "91") (pinfunction "91_91") (pintype "passive"))
    )
    (net (code "158") (name "unconnected-(J8-Pad92)") (class "Default")
      (node (ref "J8") (pin "92") (pinfunction "92_92") (pintype "passive"))
    )
    (net (code "159") (name "unconnected-(J8-Pad95)") (class "Default")
      (node (ref "J8") (pin "95") (pinfunction "95_95") (pintype "passive"))
    )
    (net (code "160") (name "unconnected-(J8-Pad96)") (class "Default")
      (node (ref "J8") (pin "96") (pinfunction "96_96") (pintype "passive"))
    )
    (net (code "161") (name "unconnected-(J8-Pad97)") (class "Default")
      (node (ref "J8") (pin "97") (pinfunction "97_97") (pintype "passive"))
    )
    (net (code "162") (name "unconnected-(J8-Pad100)") (class "Default")
      (node (ref "J8") (pin "100") (pinfunction "100_100") (pintype "passive"))
    )
    (net (code "163") (name "unconnected-(J8-Pad101)") (class "Default")
      (node (ref "J8") (pin "101") (pinfunction "101_101") (pintype "passive"))
    )
    (net (code "164") (name "unconnected-(J8-Pad104)") (class "Default")
      (node (ref "J8") (pin "104") (pinfunction "104_104") (pintype "passive"))
    )
    (net (code "165") (name "unconnected-(J8-Pad105)") (class "Default")
      (node (ref "J8") (pin "105") (pinfunction "105_105") (pintype "passive"))
    )
    (net (code "166") (name "unconnected-(J8-Pad110)") (class "Default")
      (node (ref "J8") (pin "110") (pinfunction "110_110") (pintype "passive"))
    )
    (net (code "167") (name "unconnected-(J8-Pad134)") (class "Default")
      (node (ref "J8") (pin "134") (pinfunction "134_134") (pintype "passive"))
    )
    (net (code "168") (name "unconnected-(J8-Pad157)") (class "Default")
      (node (ref "J8") (pin "157") (pinfunction "157_157") (pintype "passive"))
    )
    (net (code "169") (name "unconnected-(J8-Pad161)") (class "Default")
      (node (ref "J8") (pin "161") (pinfunction "161_161") (pintype "passive"))
    )
    (net (code "170") (name "unconnected-(J8-Pad162)") (class "Default")
      (node (ref "J8") (pin "162") (pinfunction "162_162") (pintype "passive"))
    )
    (net (code "171") (name "unconnected-(J8-Pad165)") (class "Default")
      (node (ref "J8") (pin "165") (pinfunction "165_165") (pintype "passive"))
    )
  )
)
